# 12_fit_YK.net
KiCad netlist of a schematic drawn in Altium Designer
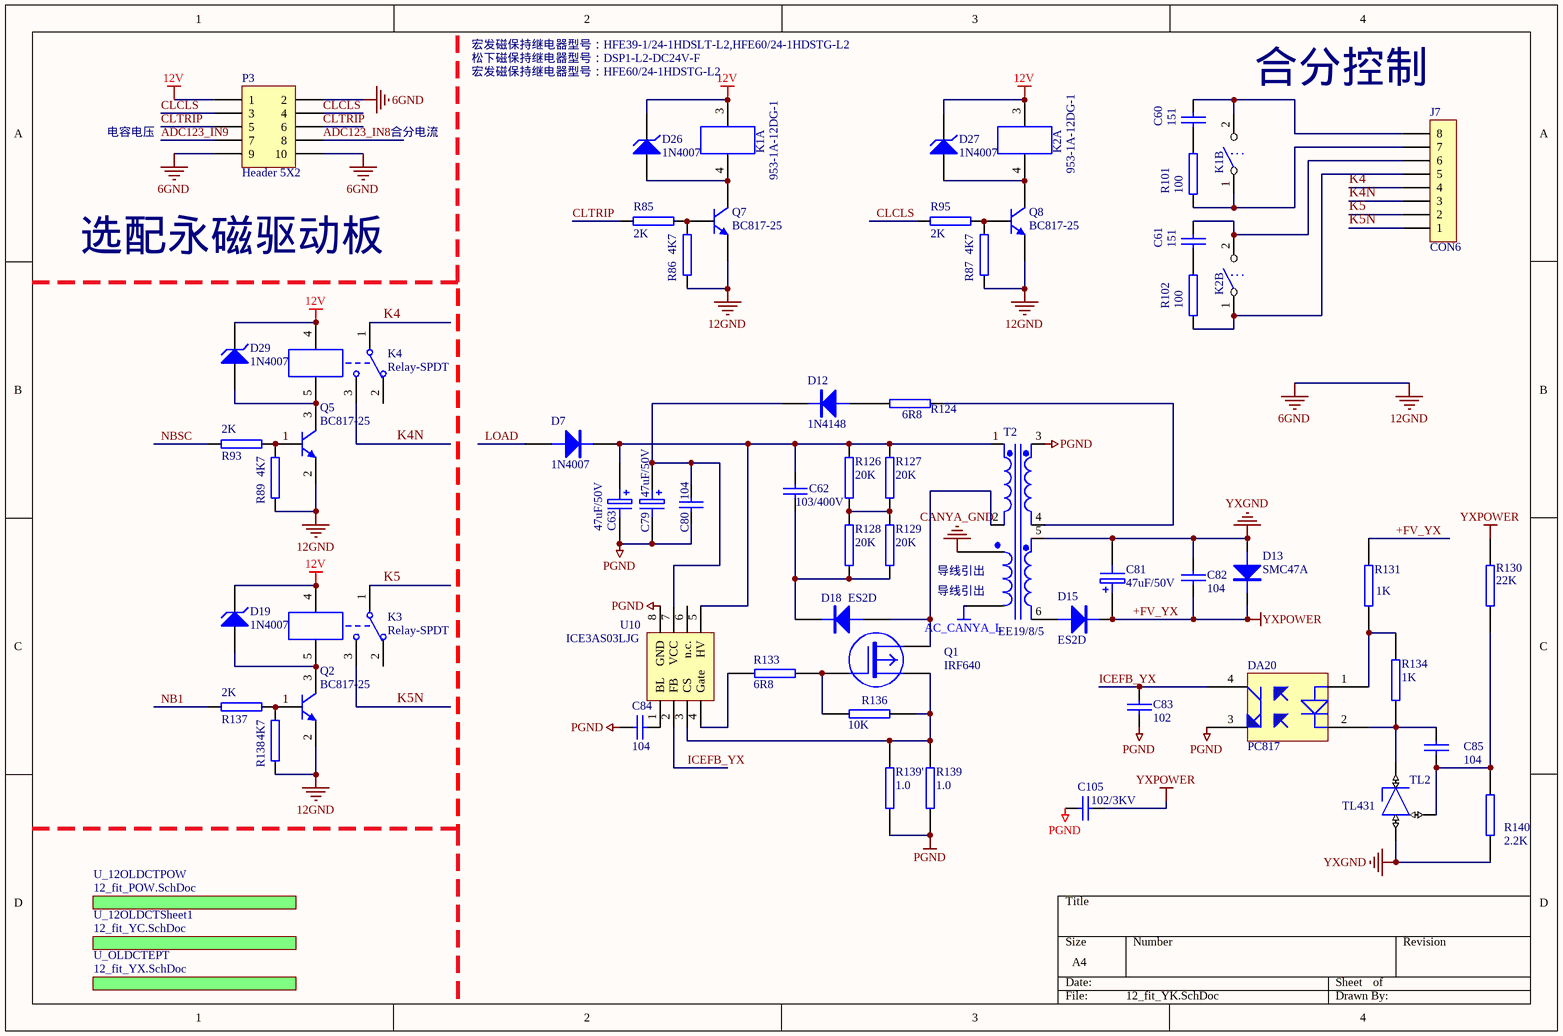
[diagram p0: 12_fit_YK.SchDoc]

(export (version "E")
  (design (tool "Eeschema 10.0.6"))
  (components
    (comp (ref "C60") (value "151") (footprint "smt:CAP_HV_10") (libsource (lib "") (part "CAP_1")))
    (comp (ref "C61") (value "151") (footprint "smt:CAP_HV_10") (libsource (lib "") (part "CAP_1")))
    (comp (ref "C62") (value "103/400V") (footprint "smt:CAP_HV_8") (libsource (lib "") (part "CAP_1")))
    (comp (ref "C63")
      (value "47uF/50V")
      (footprint "smt:47u/50V")
      (description "Electrolytic Capacitor")
      (libsource (lib "*") (part "ELECTRO1"))
    )
    (comp (ref "C79")
      (value "47uF/50V")
      (footprint "smt:47u/50V")
      (description "Electrolytic Capacitor")
      (libsource (lib "*") (part "ELECTRO1"))
    )
    (comp (ref "C80")
      (value "104")
      (footprint "smt:C1206")
      (description "Capacitor")
      (libsource (lib "*") (part "CAP"))
    )
    (comp (ref "C81")
      (value "47uF/50V")
      (footprint "smt:47u/50V")
      (description "Electrolytic Capacitor")
      (libsource (lib "*") (part "ELECTRO1"))
    )
    (comp (ref "C82")
      (value "104")
      (footprint "CBB104")
      (description "Capacitor")
      (libsource (lib "*") (part "CAP"))
    )
    (comp (ref "C83") (value "102") (footprint "smt:C1206") (libsource (lib "") (part "CAP_1")))
    (comp (ref "C84")
      (value "104")
      (footprint "smt:C1206")
      (description "Capacitor")
      (libsource (lib "*") (part "CAP"))
    )
    (comp (ref "C85")
      (value "104")
      (footprint "smt:CBB104")
      (description "Capacitor")
      (libsource (lib "*") (part "CAP"))
    )
    (comp (ref "C105")
      (value "102/3KV")
      (footprint "smt:CAP_HV_8")
      (description "Capacitor")
      (libsource (lib "*") (part "CAP"))
    )
    (comp (ref "D7")
      (value "1N4007")
      (footprint "smt:DO-214AA")
      (description "Diode")
      (libsource (lib "") (part "DIODE_1"))
    )
    (comp (ref "D12")
      (value "1N4148")
      (footprint "smt:SMT_4148")
      (description "Diode")
      (libsource (lib "") (part "DIODE_1"))
    )
    (comp (ref "D13")
      (value "SMC47A")
      (footprint "smt:DO-214AB")
      (description "Diode")
      (libsource (lib "*") (part "DIODE"))
    )
    (comp (ref "D15")
      (value "ES2D")
      (footprint "smt:DO-214AA")
      (description "Diode")
      (libsource (lib "*") (part "DIODE"))
    )
    (comp (ref "D18")
      (value "ES2D")
      (footprint "smt:DO-214AA")
      (description "Diode")
      (libsource (lib "") (part "DIODE_1"))
    )
    (comp (ref "D19")
      (value "1N4007")
      (footprint "smt:DO-214AC")
      (description "Zener Diode")
      (fields (field (name "PUBLISHER") "Altium Limited"))
      (libsource (lib "Miscellaneous Devices") (part "D Zener"))
    )
    (comp (ref "D26")
      (value "1N4007")
      (footprint "smt:DO-214AC")
      (description "Zener Diode")
      (fields (field (name "PUBLISHER") "Altium Limited"))
      (libsource (lib "Miscellaneous Devices") (part "D Zener"))
    )
    (comp (ref "D27")
      (value "1N4007")
      (footprint "smt:DO-214AC")
      (description "Zener Diode")
      (fields (field (name "PUBLISHER") "Altium Limited"))
      (libsource (lib "Miscellaneous Devices") (part "D Zener"))
    )
    (comp (ref "D29")
      (value "1N4007")
      (footprint "smt:DO-214AC")
      (description "Zener Diode")
      (fields (field (name "PUBLISHER") "Altium Limited"))
      (libsource (lib "Miscellaneous Devices") (part "D Zener"))
    )
    (comp (ref "DA20") (value "PC817") (footprint "smt:dip4") (libsource (lib "*") (part "TLP521-1")))
    (comp (ref "J7")
      (value "CON6")
      (footprint "MyCONNECTOR:XR_POWER5.08_8_弯")
      (description "Connector")
      (libsource (lib "*") (part "CON8"))
    )
    (comp (ref "K1")
      (value "953-1A-12DG-1")
      (footprint "继电器:953-1A-12DG-1")
      (description "RELAY")
      (libsource (lib "*") (part "RLY-STY1"))
    )
    (comp (ref "K2")
      (value "953-1A-12DG-1")
      (footprint "继电器:953-1A-12DG-1")
      (description "RELAY")
      (libsource (lib "*") (part "RLY-STY1"))
    )
    (comp (ref "K3")
      (value "Relay-SPDT")
      (footprint "继电器:JQX-115FA")
      (description "Single-Pole Dual-Throw Relay")
      (fields (field (name "PUBLISHER") "Altium Limited"))
      (libsource (lib "Miscellaneous Devices") (part "Relay-SPDT"))
    )
    (comp (ref "K4")
      (value "Relay-SPDT")
      (footprint "继电器:JQX-115FA")
      (description "Single-Pole Dual-Throw Relay")
      (fields (field (name "PUBLISHER") "Altium Limited"))
      (libsource (lib "Miscellaneous Devices") (part "Relay-SPDT"))
    )
    (comp (ref "P3")
      (value "Header 5X2")
      (footprint "HDR2X5")
      (description "Header, 5-Pin, Dual row")
      (fields (field (name "PUBLISHER") "Altium Limited"))
      (libsource (lib "Miscellaneous Connectors") (part "Header 5X2"))
    )
    (comp (ref "Q1") (value "IRF640") (footprint "smt:TO220-IRF540") (libsource (lib "*") (part "MOSFET-P1")))
    (comp (ref "Q2")
      (value "BC817-25")
      (footprint "smt:SOT-23")
      (description "NPN")
      (libsource (lib "Miscellaneous Devices LC") (part "SOT-23 2SC3356-T1B-A    S/YS档"))
    )
    (comp (ref "Q5")
      (value "BC817-25")
      (footprint "smt:SOT-23")
      (description "NPN")
      (libsource (lib "Miscellaneous Devices LC") (part "SOT-23 2SC3356-T1B-A    S/YS档"))
    )
    (comp (ref "Q7")
      (value "BC817-25")
      (footprint "smt:SOT-23")
      (description "NPN")
      (libsource (lib "") (part "SOT-23 2SC3356-T1B-A    S/YS档_1"))
    )
    (comp (ref "Q8")
      (value "BC817-25")
      (footprint "smt:SOT-23")
      (description "NPN")
      (libsource (lib "") (part "SOT-23 2SC3356-T1B-A    S/YS档_1"))
    )
    (comp (ref "R85") (value "2K") (footprint "smt:R1206") (libsource (lib "*") (part "RES2")))
    (comp (ref "R86") (value "4K7") (footprint "smt:R1206") (libsource (lib "*") (part "RES2")))
    (comp (ref "R87") (value "4K7") (footprint "smt:R1206") (libsource (lib "*") (part "RES2")))
    (comp (ref "R89") (value "4K7") (footprint "smt:R1206") (libsource (lib "*") (part "RES2")))
    (comp (ref "R93") (value "2K") (footprint "smt:R1206") (libsource (lib "*") (part "RES2")))
    (comp (ref "R95") (value "2K") (footprint "smt:R1206") (libsource (lib "*") (part "RES2")))
    (comp (ref "R101") (value "100") (footprint "smt:res-l5") (libsource (lib "*") (part "RES2")))
    (comp (ref "R102") (value "100") (footprint "smt:res-l5") (libsource (lib "*") (part "RES2")))
    (comp (ref "R124") (value "6R8") (footprint "smt:R1206") (libsource (lib "*") (part "RES2")))
    (comp (ref "R126") (value "20K") (footprint "smt:R1206") (libsource (lib "*") (part "RES2")))
    (comp (ref "R127") (value "20K") (footprint "smt:R1206") (libsource (lib "*") (part "RES2")))
    (comp (ref "R128") (value "20K") (footprint "smt:R1206") (libsource (lib "*") (part "RES2")))
    (comp (ref "R129") (value "20K") (footprint "smt:R1206") (libsource (lib "*") (part "RES2")))
    (comp (ref "R130") (value "22K") (footprint "smt:R1206") (libsource (lib "") (part "RES2_1")))
    (comp (ref "R131") (value "1K") (footprint "smt:R1206") (libsource (lib "") (part "RES2_1")))
    (comp (ref "R133") (value "6R8") (footprint "smt:R1206") (libsource (lib "") (part "RES2_1")))
    (comp (ref "R134") (value "1K") (footprint "smt:R1206") (libsource (lib "") (part "RES2_1")))
    (comp (ref "R136") (value "10K") (footprint "smt:R1206") (libsource (lib "") (part "RES2_1")))
    (comp (ref "R137") (value "2K") (footprint "smt:R1206") (libsource (lib "*") (part "RES2")))
    (comp (ref "R138") (value "4K7") (footprint "smt:R1206") (libsource (lib "*") (part "RES2")))
    (comp (ref "R139") (value "1.0") (footprint "smt:R2512") (libsource (lib "") (part "RES2_1")))
    (comp (ref "R139'") (value "1.0") (footprint "smt:R2512") (libsource (lib "") (part "RES2_1")))
    (comp (ref "R140") (value "2.2K") (footprint "smt:R1206") (libsource (lib "") (part "RES2_1")))
    (comp (ref "T2")
      (value "EE19/8/5")
      (footprint "变压器:EE19/8/5")
      (description "Three-winding Transformer (Ideal)")
      (fields (field (name "PUBLISHER") "Altium Limited"))
      (libsource (lib "Miscellaneous Devices") (part "Trans3 Ideal"))
    )
    (comp (ref "TL2") (value "TL431") (footprint "smt:SOT-23") (libsource (lib "*") (part "TL431")))
    (comp (ref "U10") (value "ICE3AS03LJG") (footprint "smt:SO8") (libsource (lib "*") (part "ICE3AS03LJG")))
  )
  (nets
    (net (code "1") (name "/ADC123_IN8") (class "Default")
      (node (ref "P3") (pin "8") (pinfunction "8_8") (pintype "passive"))
    )
    (net (code "2") (name "/ADC123_IN9") (class "Default")
      (node (ref "P3") (pin "7") (pinfunction "7_7") (pintype "passive"))
    )
    (net (code "3") (name "/CLCLS") (class "Default")
      (node (ref "P3") (pin "3") (pinfunction "3_3") (pintype "passive"))
      (node (ref "P3") (pin "4") (pinfunction "4_4") (pintype "passive"))
      (node (ref "R95") (pin "1") (pintype "passive"))
    )
    (net (code "4") (name "/CLTRIP") (class "Default")
      (node (ref "P3") (pin "5") (pinfunction "5_5") (pintype "passive"))
      (node (ref "P3") (pin "6") (pinfunction "6_6") (pintype "passive"))
      (node (ref "R85") (pin "1") (pintype "passive"))
    )
    (net (code "5") (name "/ICEFB_YX") (class "Default")
      (node (ref "C83") (pin "2") (pintype "passive"))
      (node (ref "DA20") (pin "4") (pintype "passive"))
      (node (ref "U10") (pin "2") (pinfunction "FB_2") (pintype "passive"))
    )
    (net (code "6") (name "/K4") (class "Default")
      (node (ref "J7") (pin "4") (pinfunction "4_4") (pintype "passive"))
      (node (ref "K4") (pin "1") (pinfunction "1_1") (pintype "passive"))
    )
    (net (code "7") (name "/K4N") (class "Default")
      (node (ref "J7") (pin "3") (pinfunction "3_3") (pintype "passive"))
      (node (ref "K4") (pin "3") (pinfunction "3_3") (pintype "passive"))
    )
    (net (code "8") (name "/K5") (class "Default")
      (node (ref "J7") (pin "2") (pinfunction "2_2") (pintype "passive"))
      (node (ref "K3") (pin "1") (pinfunction "1_1") (pintype "passive"))
    )
    (net (code "9") (name "/K5N") (class "Default")
      (node (ref "J7") (pin "1") (pinfunction "1_1") (pintype "passive"))
      (node (ref "K3") (pin "3") (pinfunction "3_3") (pintype "passive"))
    )
    (net (code "10") (name "/LOAD") (class "Default")
      (node (ref "D7") (pin "1") (pinfunction "A_1") (pintype "passive"))
    )
    (net (code "11") (name "/NB1") (class "Default") (node (ref "R137") (pin "1") (pintype "passive")))
    (net (code "12") (name "/NBSC") (class "Default") (node (ref "R93") (pin "1") (pintype "passive")))
    (net (code "13") (name "12GND") (class "Default")
      (node (ref "P3") (pin "10") (pinfunction "10_10") (pintype "passive"))
      (node (ref "P3") (pin "2") (pinfunction "2_2") (pintype "passive"))
      (node (ref "P3") (pin "9") (pinfunction "9_9") (pintype "passive"))
      (node (ref "Q2") (pin "2") (pinfunction "E_2") (pintype "passive"))
      (node (ref "Q5") (pin "2") (pinfunction "E_2") (pintype "passive"))
      (node (ref "Q7") (pin "2") (pinfunction "E_2") (pintype "passive"))
      (node (ref "Q8") (pin "2") (pinfunction "E_2") (pintype "passive"))
      (node (ref "R138") (pin "1") (pintype "passive"))
      (node (ref "R86") (pin "1") (pintype "passive"))
      (node (ref "R87") (pin "1") (pintype "passive"))
      (node (ref "R89") (pin "1") (pintype "passive"))
    )
    (net (code "14") (name "12V") (class "Default")
      (node (ref "D19") (pin "2") (pinfunction "K_2") (pintype "passive"))
      (node (ref "D26") (pin "2") (pinfunction "K_2") (pintype "passive"))
      (node (ref "D27") (pin "2") (pinfunction "K_2") (pintype "passive"))
      (node (ref "D29") (pin "2") (pinfunction "K_2") (pintype "passive"))
      (node (ref "K1") (pin "3") (pinfunction "3_3") (pintype "passive"))
      (node (ref "K2") (pin "3") (pinfunction "3_3") (pintype "passive"))
      (node (ref "K3") (pin "4") (pinfunction "4_4") (pintype "passive"))
      (node (ref "K4") (pin "4") (pinfunction "4_4") (pintype "passive"))
      (node (ref "P3") (pin "1") (pinfunction "1_1") (pintype "passive"))
    )
    (net (code "17") (name "Net-(C60-Pad1)") (class "Default")
      (node (ref "C60") (pin "1") (pintype "passive"))
      (node (ref "R101") (pin "1") (pintype "passive"))
    )
    (net (code "18") (name "Net-(C60-Pad2)") (class "Default")
      (node (ref "C60") (pin "2") (pintype "passive"))
      (node (ref "J7") (pin "8") (pinfunction "8_8") (pintype "passive"))
      (node (ref "K1") (pin "2") (pinfunction "2_2") (pintype "passive"))
    )
    (net (code "19") (name "Net-(C61-Pad1)") (class "Default")
      (node (ref "C61") (pin "1") (pintype "passive"))
      (node (ref "J7") (pin "6") (pinfunction "6_6") (pintype "passive"))
      (node (ref "K2") (pin "2") (pinfunction "2_2") (pintype "passive"))
    )
    (net (code "20") (name "Net-(C61-Pad2)") (class "Default")
      (node (ref "C61") (pin "2") (pintype "passive"))
      (node (ref "R102") (pin "1") (pintype "passive"))
    )
    (net (code "21") (name "Net-(D7-K)") (class "Default")
      (node (ref "C62") (pin "2") (pintype "passive"))
      (node (ref "C63") (pin "1") (pinfunction "1_1") (pintype "passive"))
      (node (ref "D7") (pin "2") (pinfunction "K_2") (pintype "passive"))
      (node (ref "R126") (pin "2") (pintype "passive"))
      (node (ref "R127") (pin "2") (pintype "passive"))
      (node (ref "T2") (pin "1") (pinfunction "Pri+_1") (pintype "passive"))
      (node (ref "U10") (pin "5") (pinfunction "HV_5") (pintype "passive"))
    )
    (net (code "22") (name "Net-(D12-A)") (class "Default")
      (node (ref "D12") (pin "1") (pinfunction "A_1") (pintype "passive"))
      (node (ref "R124") (pin "1") (pintype "passive"))
    )
    (net (code "23") (name "Net-(D12-K)") (class "Default")
      (node (ref "C79") (pin "1") (pinfunction "1_1") (pintype "passive"))
      (node (ref "C80") (pin "2") (pinfunction "2_2") (pintype "passive"))
      (node (ref "D12") (pin "2") (pinfunction "K_2") (pintype "passive"))
      (node (ref "U10") (pin "7") (pinfunction "VCC_7") (pintype "passive"))
    )
    (net (code "24") (name "Net-(D15-A)") (class "Default")
      (node (ref "D15") (pin "1") (pinfunction "A_1") (pintype "passive"))
      (node (ref "T2") (pin "6") (pinfunction "Sec2-_6") (pintype "passive"))
    )
    (net (code "25") (name "Net-(D18-A)") (class "Default")
      (node (ref "D18") (pin "1") (pinfunction "A_1") (pintype "passive"))
      (node (ref "Q1") (pin "2") (pinfunction "D_2") (pintype "passive"))
      (node (ref "T2") (pin "2") (pinfunction "Pri-_2") (pintype "passive"))
    )
    (net (code "26") (name "Net-(D18-K)") (class "Default")
      (node (ref "C62") (pin "1") (pintype "passive"))
      (node (ref "D18") (pin "2") (pinfunction "K_2") (pintype "passive"))
      (node (ref "R128") (pin "1") (pintype "passive"))
      (node (ref "R129") (pin "1") (pintype "passive"))
    )
    (net (code "27") (name "Net-(D19-A)") (class "Default")
      (node (ref "D19") (pin "1") (pinfunction "A_1") (pintype "passive"))
      (node (ref "K3") (pin "5") (pinfunction "5_5") (pintype "passive"))
      (node (ref "Q2") (pin "3") (pinfunction "C_3") (pintype "passive"))
    )
    (net (code "28") (name "Net-(D26-A)") (class "Default")
      (node (ref "D26") (pin "1") (pinfunction "A_1") (pintype "passive"))
      (node (ref "K1") (pin "4") (pinfunction "4_4") (pintype "passive"))
      (node (ref "Q7") (pin "3") (pinfunction "C_3") (pintype "passive"))
    )
    (net (code "29") (name "Net-(D27-A)") (class "Default")
      (node (ref "D27") (pin "1") (pinfunction "A_1") (pintype "passive"))
      (node (ref "K2") (pin "4") (pinfunction "4_4") (pintype "passive"))
      (node (ref "Q8") (pin "3") (pinfunction "C_3") (pintype "passive"))
    )
    (net (code "30") (name "Net-(D29-A)") (class "Default")
      (node (ref "D29") (pin "1") (pinfunction "A_1") (pintype "passive"))
      (node (ref "K4") (pin "5") (pinfunction "5_5") (pintype "passive"))
      (node (ref "Q5") (pin "3") (pinfunction "C_3") (pintype "passive"))
    )
    (net (code "31") (name "Net-(DA20-Pad1)") (class "Default")
      (node (ref "DA20") (pin "1") (pintype "passive"))
      (node (ref "R131") (pin "1") (pinfunction "1_1") (pintype "passive"))
      (node (ref "R134") (pin "2") (pinfunction "2_2") (pintype "passive"))
    )
    (net (code "32") (name "Net-(J7-Pad5)") (class "Default")
      (node (ref "J7") (pin "5") (pinfunction "5_5") (pintype "passive"))
      (node (ref "K2") (pin "1") (pinfunction "1_1") (pintype "passive"))
      (node (ref "R102") (pin "2") (pintype "passive"))
    )
    (net (code "33") (name "Net-(J7-Pad7)") (class "Default")
      (node (ref "J7") (pin "7") (pinfunction "7_7") (pintype "passive"))
      (node (ref "K1") (pin "1") (pinfunction "1_1") (pintype "passive"))
      (node (ref "R101") (pin "2") (pintype "passive"))
    )
    (net (code "34") (name "Net-(Q1-G)") (class "Default")
      (node (ref "Q1") (pin "1") (pinfunction "G_1") (pintype "passive"))
      (node (ref "R133") (pin "1") (pinfunction "1_1") (pintype "passive"))
      (node (ref "R136") (pin "2") (pinfunction "2_2") (pintype "passive"))
    )
    (net (code "35") (name "Net-(Q1-S)") (class "Default")
      (node (ref "Q1") (pin "3") (pinfunction "S_3") (pintype "passive"))
      (node (ref "R136") (pin "1") (pinfunction "1_1") (pintype "passive"))
      (node (ref "R139") (pin "2") (pinfunction "2_2") (pintype "passive"))
      (node (ref "R139'") (pin "2") (pinfunction "2_2") (pintype "passive"))
      (node (ref "U10") (pin "3") (pinfunction "CS_3") (pintype "passive"))
    )
    (net (code "36") (name "Net-(Q2-B)") (class "Default")
      (node (ref "Q2") (pin "1") (pinfunction "B_1") (pintype "passive"))
      (node (ref "R137") (pin "2") (pintype "passive"))
      (node (ref "R138") (pin "2") (pintype "passive"))
    )
    (net (code "37") (name "Net-(Q5-B)") (class "Default")
      (node (ref "Q5") (pin "1") (pinfunction "B_1") (pintype "passive"))
      (node (ref "R89") (pin "2") (pintype "passive"))
      (node (ref "R93") (pin "2") (pintype "passive"))
    )
    (net (code "38") (name "Net-(Q7-B)") (class "Default")
      (node (ref "Q7") (pin "1") (pinfunction "B_1") (pintype "passive"))
      (node (ref "R85") (pin "2") (pintype "passive"))
      (node (ref "R86") (pin "2") (pintype "passive"))
    )
    (net (code "39") (name "Net-(Q8-B)") (class "Default")
      (node (ref "Q8") (pin "1") (pinfunction "B_1") (pintype "passive"))
      (node (ref "R87") (pin "2") (pintype "passive"))
      (node (ref "R95") (pin "2") (pintype "passive"))
    )
    (net (code "40") (name "Net-(R126-Pad1)") (class "Default")
      (node (ref "R126") (pin "1") (pintype "passive"))
      (node (ref "R127") (pin "1") (pintype "passive"))
      (node (ref "R128") (pin "2") (pintype "passive"))
      (node (ref "R129") (pin "2") (pintype "passive"))
    )
    (net (code "41") (name "Net-(T2-Sec1-)") (class "Default")
      (node (ref "R124") (pin "2") (pintype "passive"))
      (node (ref "T2") (pin "4") (pinfunction "Sec1-_4") (pintype "passive"))
    )
    (net (code "42") (name "Net-(TL2-K)") (class "Default")
      (node (ref "C85") (pin "1") (pinfunction "1_1") (pintype "passive"))
      (node (ref "DA20") (pin "2") (pintype "passive"))
      (node (ref "R134") (pin "1") (pinfunction "1_1") (pintype "passive"))
      (node (ref "TL2") (pin "1") (pinfunction "K_1") (pintype "bidirectional"))
    )
    (net (code "43") (name "Net-(TL2-R)") (class "Default")
      (node (ref "C85") (pin "2") (pinfunction "2_2") (pintype "passive"))
      (node (ref "R130") (pin "1") (pinfunction "1_1") (pintype "passive"))
      (node (ref "R140") (pin "2") (pinfunction "2_2") (pintype "passive"))
      (node (ref "TL2") (pin "2") (pinfunction "R_2") (pintype "bidirectional"))
    )
    (net (code "44") (name "Net-(U10-BL)") (class "Default")
      (node (ref "C84") (pin "2") (pinfunction "2_2") (pintype "passive"))
      (node (ref "U10") (pin "1") (pinfunction "BL_1") (pintype "passive"))
    )
    (net (code "45") (name "Net-(U10-Gate)") (class "Default")
      (node (ref "R133") (pin "2") (pinfunction "2_2") (pintype "passive"))
      (node (ref "U10") (pin "4") (pinfunction "Gate_4") (pintype "passive"))
    )
    (net (code "46") (name "PGND") (class "Default")
      (node (ref "C105") (pin "1") (pinfunction "1_1") (pintype "passive"))
      (node (ref "C63") (pin "2") (pinfunction "2_2") (pintype "passive"))
      (node (ref "C79") (pin "2") (pinfunction "2_2") (pintype "passive"))
      (node (ref "C80") (pin "1") (pinfunction "1_1") (pintype "passive"))
      (node (ref "C83") (pin "1") (pintype "passive"))
      (node (ref "C84") (pin "1") (pinfunction "1_1") (pintype "passive"))
      (node (ref "DA20") (pin "3") (pintype "passive"))
      (node (ref "R139") (pin "1") (pinfunction "1_1") (pintype "passive"))
      (node (ref "R139'") (pin "1") (pinfunction "1_1") (pintype "passive"))
      (node (ref "T2") (pin "3") (pinfunction "Sec1+_3") (pintype "passive"))
      (node (ref "U10") (pin "8") (pinfunction "GND_8") (pintype "passive"))
    )
    (net (code "47") (name "YXGND") (class "Default")
      (node (ref "C81") (pin "2") (pinfunction "2_2") (pintype "passive"))
      (node (ref "C82") (pin "2") (pinfunction "2_2") (pintype "passive"))
      (node (ref "D13") (pin "1") (pinfunction "A_1") (pintype "passive"))
      (node (ref "R140") (pin "1") (pinfunction "1_1") (pintype "passive"))
      (node (ref "T2") (pin "5") (pinfunction "Sec2+_5") (pintype "passive"))
      (node (ref "TL2") (pin "3") (pinfunction "A_3") (pintype "bidirectional"))
    )
    (net (code "48") (name "YXPOWER") (class "Default")
      (node (ref "C105") (pin "2") (pinfunction "2_2") (pintype "passive"))
      (node (ref "C81") (pin "1") (pinfunction "1_1") (pintype "passive"))
      (node (ref "C82") (pin "1") (pinfunction "1_1") (pintype "passive"))
      (node (ref "D13") (pin "2") (pinfunction "K_2") (pintype "passive"))
      (node (ref "D15") (pin "2") (pinfunction "K_2") (pintype "passive"))
      (node (ref "R130") (pin "2") (pinfunction "2_2") (pintype "passive"))
      (node (ref "R131") (pin "2") (pinfunction "2_2") (pintype "passive"))
    )
    (net (code "49") (name "unconnected-(K3-Pad2)") (class "Default")
      (node (ref "K3") (pin "2") (pinfunction "2_2") (pintype "passive"))
    )
    (net (code "50") (name "unconnected-(K4-Pad2)") (class "Default")
      (node (ref "K4") (pin "2") (pinfunction "2_2") (pintype "passive"))
    )
    (net (code "51") (name "unconnected-(U10-n.c.-Pad6)") (class "Default")
      (node (ref "U10") (pin "6") (pinfunction "n.c._6") (pintype "passive"))
    )
  )
)
